# Simple-Transmitter-BC547.net
KiCad netlist of a schematic drawn in EAGLE
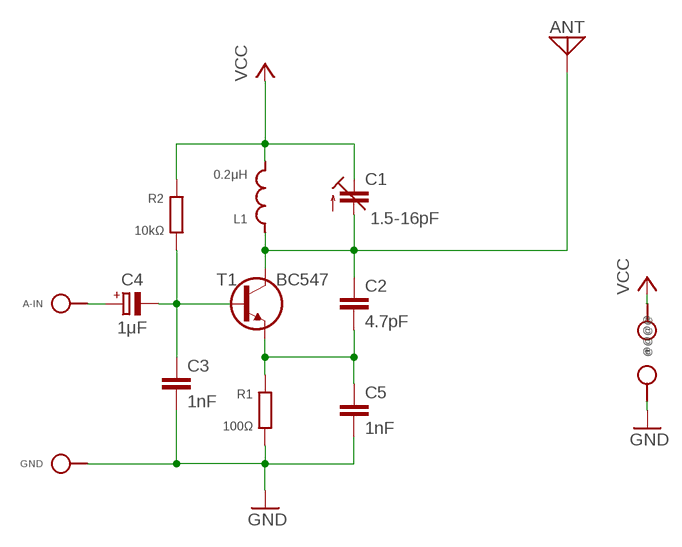
[diagram p0: schematic, sheet 1]

(export (version "E")
  (design (tool "Eeschema 10.0.6"))
  (components
    (comp (ref "+")
      (value "SPAD")
      (footprint "eagle-import:SPAD")
      (libsource (lib "eagle-import") (part "SPAD"))
    )
    (comp (ref "@@@@")
      (value "SPAD")
      (footprint "eagle-import:SPAD")
      (libsource (lib "eagle-import") (part "SPAD"))
    )
    (comp (ref "A-IN")
      (value "SPAD")
      (footprint "eagle-import:SPAD")
      (libsource (lib "eagle-import") (part "SPAD"))
    )
    (comp (ref "ANT")
      (value "ANT")
      (footprint "eagle-import:SPAD")
      (libsource (lib "eagle-import") (part "ANT"))
    )
    (comp (ref "C1")
      (value "1.5-16pF")
      (footprint "eagle-import:TRIM808-45")
      (libsource (lib "eagle-import") (part "C-TR-PH20127-45-2P23"))
    )
    (comp (ref "C2")
      (value "4.7pF")
      (footprint "eagle-import:C050-020X036-M")
      (libsource (lib "eagle-import") (part "C050-020X036-M"))
    )
    (comp (ref "C3")
      (value "1nF")
      (footprint "eagle-import:C050-020X036")
      (libsource (lib "eagle-import") (part "C050-020X036"))
    )
    (comp (ref "C4")
      (value "1μF")
      (footprint "eagle-import:E2,5-3")
      (libsource (lib "eagle-import") (part "CPOLE2,5-3"))
    )
    (comp (ref "C5")
      (value "1nF")
      (footprint "eagle-import:C050-020X036")
      (libsource (lib "eagle-import") (part "C050-020X036"))
    )
    (comp (ref "GND")
      (value "SPAD")
      (footprint "eagle-import:SPAD")
      (libsource (lib "eagle-import") (part "SPAD"))
    )
    (comp (ref "L1")
      (value "0.2μH")
      (footprint "eagle-import:L-04_8V")
      (libsource (lib "eagle-import") (part "L-SHORT04/7"))
    )
    (comp (ref "R1")
      (value "100Ω")
      (footprint "eagle-import:0202V")
      (libsource (lib "eagle-import") (part "R0202V"))
    )
    (comp (ref "R2")
      (value "10kΩ")
      (footprint "eagle-import:0204_10-V")
      (libsource (lib "eagle-import") (part "R0204/10-V"))
    )
    (comp (ref "T1")
      (value "BC547")
      (footprint "eagle-import:TO92-CBE")
      (libsource (lib "eagle-import") (part "BC547CBE"))
    )
  )
  (nets
    (net (code "1") (name "GND") (class "Default")
      (node (ref "@@@@") (pin "1") (pinfunction "P$1_1") (pintype "bidirectional"))
      (node (ref "C3") (pin "2") (pinfunction "2_2") (pintype "passive"))
      (node (ref "C5") (pin "2") (pinfunction "2_2") (pintype "passive"))
      (node (ref "GND") (pin "1") (pinfunction "P$1_1") (pintype "bidirectional"))
      (node (ref "R1") (pin "1") (pinfunction "1_1") (pintype "passive"))
    )
    (net (code "2") (name "Net-(A-IN-P$1)") (class "Default")
      (node (ref "A-IN") (pin "1") (pinfunction "P$1_1") (pintype "bidirectional"))
      (node (ref "C4") (pin "+") (pinfunction "+_+") (pintype "passive"))
    )
    (net (code "3") (name "Net-(C1-E)") (class "Default")
      (node (ref "ANT") (pin "1") (pinfunction "1_1") (pintype "output"))
      (node (ref "C1") (pin "2") (pinfunction "E_2") (pintype "passive"))
      (node (ref "C2") (pin "1") (pinfunction "1_1") (pintype "passive"))
      (node (ref "L1") (pin "1") (pinfunction "1_1") (pintype "passive"))
      (node (ref "T1") (pin "C") (pinfunction "C_C") (pintype "passive"))
    )
    (net (code "4") (name "Net-(C2-Pad2)") (class "Default")
      (node (ref "C2") (pin "2") (pinfunction "2_2") (pintype "passive"))
      (node (ref "C5") (pin "1") (pinfunction "1_1") (pintype "passive"))
      (node (ref "R1") (pin "2") (pinfunction "2_2") (pintype "passive"))
      (node (ref "T1") (pin "E") (pinfunction "E_E") (pintype "passive"))
    )
    (net (code "5") (name "Net-(C3-Pad1)") (class "Default")
      (node (ref "C3") (pin "1") (pinfunction "1_1") (pintype "passive"))
      (node (ref "C4") (pin "-") (pinfunction "-_-") (pintype "passive"))
      (node (ref "R2") (pin "1") (pinfunction "1_1") (pintype "passive"))
      (node (ref "T1") (pin "B") (pinfunction "B_B") (pintype "passive"))
    )
    (net (code "6") (name "VCC") (class "Default")
      (node (ref "+") (pin "1") (pinfunction "P$1_1") (pintype "bidirectional"))
      (node (ref "C1") (pin "3") (pinfunction "A_3") (pintype "passive"))
      (node (ref "L1") (pin "2") (pinfunction "2_2") (pintype "passive"))
      (node (ref "R2") (pin "2") (pinfunction "2_2") (pintype "passive"))
    )
  )
)
